# Input.net
KiCad netlist of a schematic drawn in Altium Designer
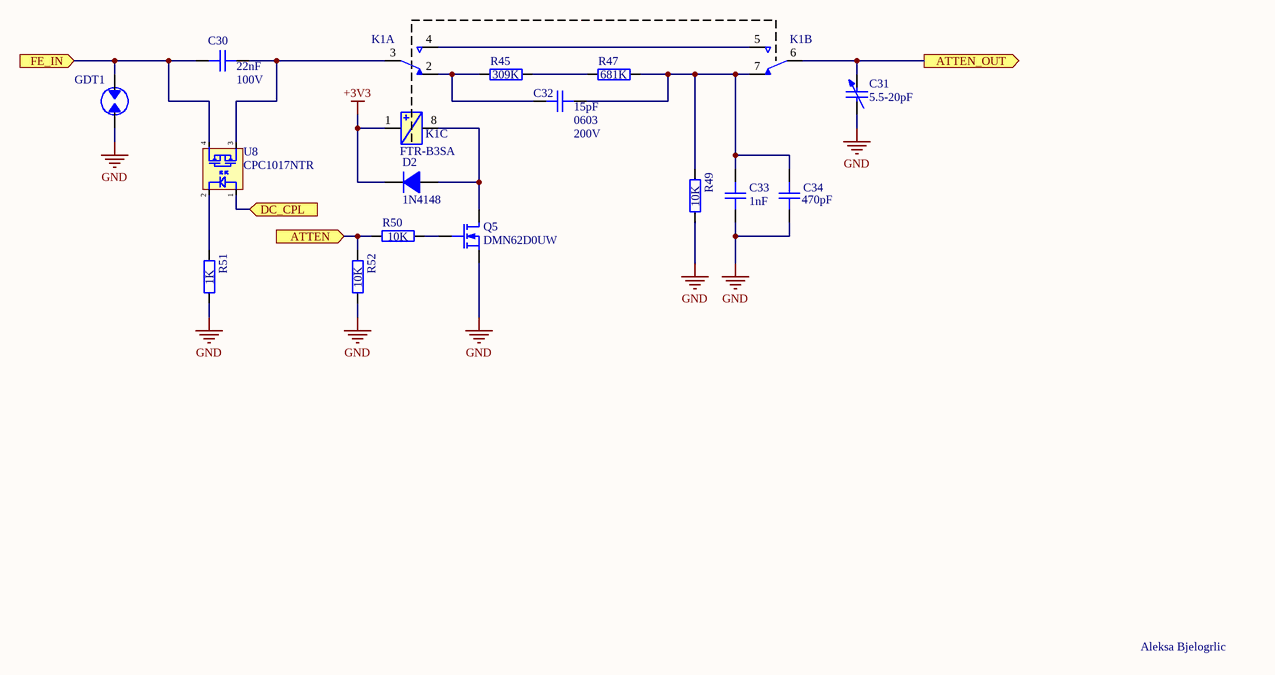
[diagram p0: Input.SchDoc]

(export (version "E")
  (design (tool "Eeschema 10.0.6"))
  (components
    (comp (ref "C30")
      (value "22nF")
      (footprint "GEN_C_0603")
      (fields (field (name "VOLTAGE RATING") "100V"))
      (libsource (lib "DSO") (part "CAP 22nF 100V X7R 0603"))
    )
    (comp (ref "C31")
      (value "5.5-20pF")
      (footprint "EW_TRIMCAP")
      (libsource (lib "DSO") (part "CAP TRIMMER 5.5-20PF 500V"))
    )
    (comp (ref "C32")
      (value "15pF")
      (footprint "GEN_C_0603")
      (fields (field (name "PACKAGE") "0603") (field (name "VOLTAGE RATING") "200V"))
      (libsource (lib "DSO") (part "CAP 15pF 200V C0G 0603"))
    )
    (comp (ref "C33")
      (value "1nF")
      (footprint "GEN_C_0402")
      (libsource (lib "DSO") (part "CAP 1nF 50V C0G 0402"))
    )
    (comp (ref "C34")
      (value "470pF")
      (footprint "GEN_C_0402")
      (libsource (lib "DSO") (part "CAP 470pF 50V C0G 0402"))
    )
    (comp (ref "D2") (value "1N4148") (footprint "GEN_SOD_323") (libsource (lib "DSO") (part "DIODE 1N4148")))
    (comp (ref "GDT1") (value "GDT") (footprint "BOU_2051") (libsource (lib "DSO") (part "GDT 90V")))
    (comp (ref "K1")
      (value "FTR-B3SA")
      (footprint "FUJ_FTR-B3SA")
      (libsource (lib "DSO") (part "RELAY DPDT-NO FTR-B3SA"))
    )
    (comp (ref "Q5")
      (value "DMN62D0UW")
      (footprint "GEN_SOT_323")
      (libsource (lib "DSO") (part "NMOS DMN62D0UW"))
    )
    (comp (ref "R45")
      (value "309K")
      (footprint "GEN_R_0402")
      (fields (field (name "TOLERANCE") "1%"))
      (libsource (lib "DSO") (part "RES 309K OHM 1% 1/16W 0402"))
    )
    (comp (ref "R47")
      (value "681K")
      (footprint "GEN_R_0402")
      (fields (field (name "TOLERANCE") "1%"))
      (libsource (lib "DSO") (part "RES 681K OHM 1% 1/16W 0402"))
    )
    (comp (ref "R49")
      (value "10K")
      (footprint "GEN_R_0402")
      (fields (field (name "TOLERANCE") "1%"))
      (libsource (lib "DSO") (part "RES 10K OHM 1% 1/10W 0402"))
    )
    (comp (ref "R50")
      (value "10K")
      (footprint "GEN_R_0402")
      (fields (field (name "TOLERANCE") "1%"))
      (libsource (lib "") (part "RES 10K OHM 1% 1/10W 0402_1"))
    )
    (comp (ref "R51")
      (value "1K")
      (footprint "GEN_R_0402")
      (fields (field (name "TOLERANCE") "1%"))
      (libsource (lib "DSO") (part "RES 1K OHM 1% 1/10W 0402"))
    )
    (comp (ref "R52")
      (value "10K")
      (footprint "GEN_R_0402")
      (fields (field (name "TOLERANCE") "1%"))
      (libsource (lib "DSO") (part "RES 10K OHM 1% 1/10W 0402"))
    )
    (comp (ref "U8")
      (value "CPC1017NTR")
      (footprint "IXY_CPC1017")
      (libsource (lib "DSO") (part "SSR CPC1017NTR"))
    )
  )
  (nets
    (net (code "1") (name "+3V3") (class "Default")
      (node (ref "D2") (pin "1") (pinfunction "K_1") (pintype "passive"))
      (node (ref "K1") (pin "1") (pinfunction "1_1") (pintype "passive"))
    )
    (net (code "2") (name "/ATTEN") (class "Default")
      (node (ref "R50") (pin "2") (pinfunction "2_2") (pintype "passive"))
      (node (ref "R52") (pin "2") (pinfunction "2_2") (pintype "passive"))
    )
    (net (code "3") (name "/ATTEN_OUT") (class "Default")
      (node (ref "C31") (pin "1") (pinfunction "1_1") (pintype "passive"))
      (node (ref "K1") (pin "6") (pinfunction "6_6") (pintype "passive"))
    )
    (net (code "4") (name "/DC_CPL") (class "Default")
      (node (ref "U8") (pin "1") (pinfunction "1_1") (pintype "passive"))
    )
    (net (code "5") (name "/FE_IN") (class "Default")
      (node (ref "C30") (pin "2") (pinfunction "2_2") (pintype "passive"))
      (node (ref "GDT1") (pin "1") (pinfunction "1_1") (pintype "passive"))
      (node (ref "U8") (pin "4") (pinfunction "4_4") (pintype "passive"))
    )
    (net (code "6") (name "GND") (class "Default")
      (node (ref "C31") (pin "2") (pinfunction "2_2") (pintype "passive"))
      (node (ref "C33") (pin "1") (pinfunction "1_1") (pintype "passive"))
      (node (ref "C34") (pin "1") (pinfunction "1_1") (pintype "passive"))
      (node (ref "GDT1") (pin "2") (pinfunction "2_2") (pintype "passive"))
      (node (ref "Q5") (pin "3") (pinfunction "S_3") (pintype "passive"))
      (node (ref "R49") (pin "1") (pinfunction "1_1") (pintype "passive"))
      (node (ref "R51") (pin "1") (pinfunction "1_1") (pintype "passive"))
      (node (ref "R52") (pin "1") (pinfunction "1_1") (pintype "passive"))
    )
    (net (code "7") (name "Net-(C30-Pad1)") (class "Default")
      (node (ref "C30") (pin "1") (pinfunction "1_1") (pintype "passive"))
      (node (ref "K1") (pin "3") (pinfunction "3_3") (pintype "passive"))
      (node (ref "U8") (pin "3") (pinfunction "3_3") (pintype "passive"))
    )
    (net (code "8") (name "Net-(C32-Pad1)") (class "Default")
      (node (ref "C32") (pin "1") (pinfunction "1_1") (pintype "passive"))
      (node (ref "C33") (pin "2") (pinfunction "2_2") (pintype "passive"))
      (node (ref "C34") (pin "2") (pinfunction "2_2") (pintype "passive"))
      (node (ref "K1") (pin "7") (pinfunction "7_7") (pintype "passive"))
      (node (ref "R47") (pin "2") (pinfunction "2_2") (pintype "passive"))
      (node (ref "R49") (pin "2") (pinfunction "2_2") (pintype "passive"))
    )
    (net (code "9") (name "Net-(C32-Pad2)") (class "Default")
      (node (ref "C32") (pin "2") (pinfunction "2_2") (pintype "passive"))
      (node (ref "K1") (pin "2") (pinfunction "2_2") (pintype "passive"))
      (node (ref "R45") (pin "1") (pinfunction "1_1") (pintype "passive"))
    )
    (net (code "10") (name "Net-(D2-A)") (class "Default")
      (node (ref "D2") (pin "2") (pinfunction "A_2") (pintype "passive"))
      (node (ref "K1") (pin "8") (pinfunction "8_8") (pintype "passive"))
      (node (ref "Q5") (pin "1") (pinfunction "D_1") (pintype "passive"))
    )
    (net (code "11") (name "Net-(K1-Pad4)") (class "Default")
      (node (ref "K1") (pin "4") (pinfunction "4_4") (pintype "passive"))
      (node (ref "K1") (pin "5") (pinfunction "5_5") (pintype "passive"))
    )
    (net (code "12") (name "Net-(Q5-G)") (class "Default")
      (node (ref "Q5") (pin "2") (pinfunction "G_2") (pintype "passive"))
      (node (ref "R50") (pin "1") (pinfunction "1_1") (pintype "passive"))
    )
    (net (code "13") (name "Net-(R45-Pad2)") (class "Default")
      (node (ref "R45") (pin "2") (pinfunction "2_2") (pintype "passive"))
      (node (ref "R47") (pin "1") (pinfunction "1_1") (pintype "passive"))
    )
    (net (code "14") (name "Net-(R51-Pad2)") (class "Default")
      (node (ref "R51") (pin "2") (pinfunction "2_2") (pintype "passive"))
      (node (ref "U8") (pin "2") (pinfunction "2_2") (pintype "passive"))
    )
  )
)
